# rapidshark.net
KiCad netlist of a schematic drawn in EAGLE
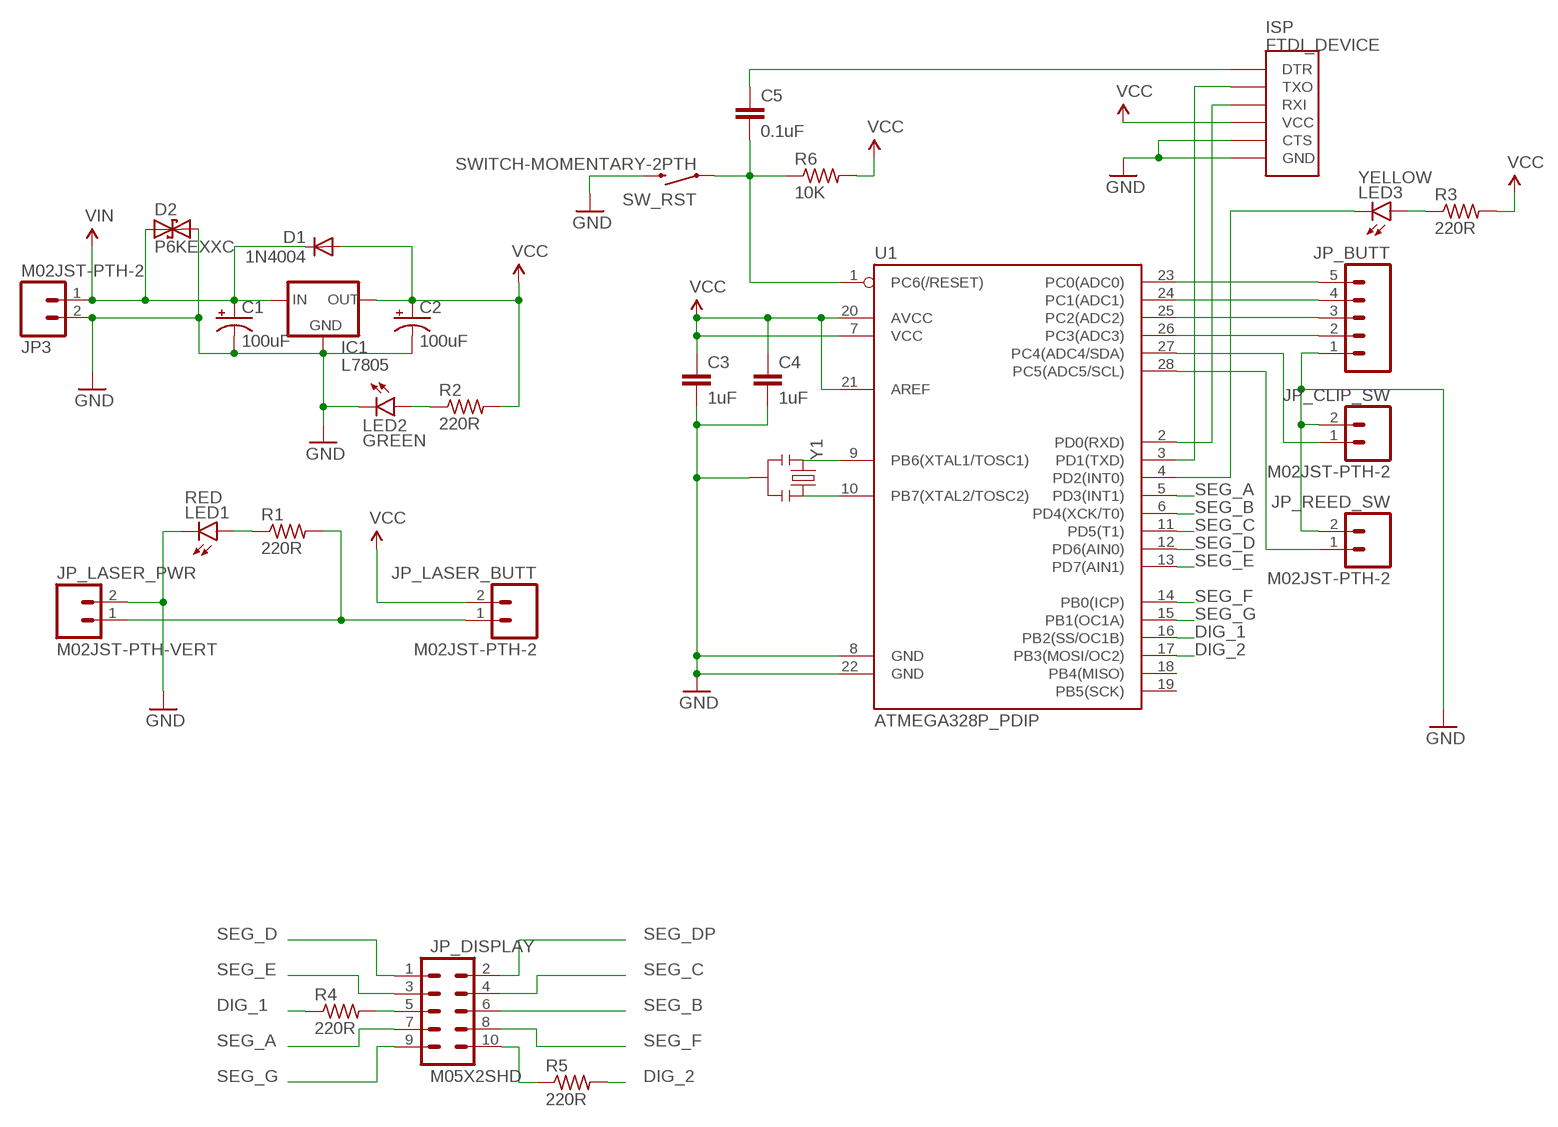
[diagram p0: schematic, sheet 1]

(export (version "E")
  (design (tool "Eeschema 10.0.6"))
  (components
    (comp (ref "C1")
      (value "100uF")
      (footprint "eagle-import:E2,5-6")
      (libsource (lib "eagle-import") (part "CPOL-USE2.5-6"))
    )
    (comp (ref "C2")
      (value "100uF")
      (footprint "eagle-import:E2,5-6")
      (libsource (lib "eagle-import") (part "CPOL-USE2.5-6"))
    )
    (comp (ref "C3")
      (value "1uF")
      (footprint "eagle-import:C025-025X050")
      (libsource (lib "eagle-import") (part "C-EU025-025X050"))
    )
    (comp (ref "C4")
      (value "1uF")
      (footprint "eagle-import:C050-024X044")
      (libsource (lib "eagle-import") (part "C-EU050-024X044"))
    )
    (comp (ref "C5")
      (value "0.1uF")
      (footprint "eagle-import:C050-024X044")
      (libsource (lib "eagle-import") (part "C-EU050-024X044"))
    )
    (comp (ref "D1")
      (value "1N4004")
      (footprint "eagle-import:DO41-10")
      (libsource (lib "eagle-import") (part "1N4004"))
    )
    (comp (ref "D2")
      (value "P6KEXXC")
      (footprint "eagle-import:CB417-15")
      (libsource (lib "eagle-import") (part "P6KEXXC"))
    )
    (comp (ref "IC1")
      (value "L7805")
      (footprint "eagle-import:TO-220-ALT")
      (libsource (lib "eagle-import") (part "V_REG_78XX-TO-220"))
    )
    (comp (ref "ISP")
      (value "FTDI_DEVICE")
      (footprint "eagle-import:FTDI_DEVICE_SIDE")
      (libsource (lib "eagle-import") (part "FTDI_DEVICE"))
    )
    (comp (ref "JP3")
      (value "M02JST-PTH-2")
      (footprint "eagle-import:JST-2-PTH")
      (libsource (lib "eagle-import") (part "M02JST-PTH-2"))
    )
    (comp (ref "JP_BUTT")
      (value "M05PTH")
      (footprint "eagle-import:1X05")
      (libsource (lib "eagle-import") (part "M05PTH"))
    )
    (comp (ref "JP_CLIP_SW")
      (value "M02JST-PTH-2")
      (footprint "eagle-import:JST-2-PTH")
      (libsource (lib "eagle-import") (part "M02JST-PTH-2"))
    )
    (comp (ref "JP_DISPLAY")
      (value "M05X2SHD")
      (footprint "eagle-import:2X5-SHROUDED")
      (libsource (lib "eagle-import") (part "M05X2SHD"))
    )
    (comp (ref "JP_LASER_BUTT")
      (value "M02JST-PTH-2")
      (footprint "eagle-import:JST-2-PTH")
      (libsource (lib "eagle-import") (part "M02JST-PTH-2"))
    )
    (comp (ref "JP_LASER_PWR")
      (value "M02JST-PTH-VERT")
      (footprint "eagle-import:JST-2-PTH-VERT")
      (libsource (lib "eagle-import") (part "M02JST-PTH-VERT"))
    )
    (comp (ref "JP_REED_SW")
      (value "M02JST-PTH-2")
      (footprint "eagle-import:JST-2-PTH")
      (libsource (lib "eagle-import") (part "M02JST-PTH-2"))
    )
    (comp (ref "LED1")
      (value "RED")
      (footprint "eagle-import:LED3MM")
      (libsource (lib "eagle-import") (part "LED3MM"))
    )
    (comp (ref "LED2")
      (value "GREEN")
      (footprint "eagle-import:LED3MM")
      (libsource (lib "eagle-import") (part "LED3MM"))
    )
    (comp (ref "LED3")
      (value "YELLOW")
      (footprint "eagle-import:LED3MM")
      (libsource (lib "eagle-import") (part "LED3MM"))
    )
    (comp (ref "R1")
      (value "220R")
      (footprint "eagle-import:0204_7")
      (libsource (lib "eagle-import") (part "R-US_0204/7"))
    )
    (comp (ref "R2")
      (value "220R")
      (footprint "eagle-import:0204_7")
      (libsource (lib "eagle-import") (part "R-US_0204/7"))
    )
    (comp (ref "R3")
      (value "220R")
      (footprint "eagle-import:0204_7")
      (libsource (lib "eagle-import") (part "R-US_0204/7"))
    )
    (comp (ref "R4")
      (value "220R")
      (footprint "eagle-import:0204_7")
      (libsource (lib "eagle-import") (part "R-US_0204/7"))
    )
    (comp (ref "R5")
      (value "220R")
      (footprint "eagle-import:0204_7")
      (libsource (lib "eagle-import") (part "R-US_0204/7"))
    )
    (comp (ref "R6")
      (value "10K")
      (footprint "eagle-import:0204_7")
      (libsource (lib "eagle-import") (part "R-US_0204/7"))
    )
    (comp (ref "SW_RST")
      (value "SWITCH-MOMENTARY-2PTH")
      (footprint "eagle-import:TACTILE-PTH")
      (libsource (lib "eagle-import") (part "SWITCH-MOMENTARY-2PTH"))
    )
    (comp (ref "U1")
      (value "ATMEGA328P_PDIP")
      (footprint "eagle-import:DIL28-3")
      (libsource (lib "eagle-import") (part "ATMEGA328P_PDIP"))
    )
    (comp (ref "Y1")
      (value "RESONATORPTH")
      (footprint "eagle-import:RESONATOR-PTH")
      (libsource (lib "eagle-import") (part "RESONATORPTH"))
    )
  )
  (nets
    (net (code "1") (name "/DIG_1") (class "Default")
      (node (ref "R4") (pin "1") (pinfunction "1_1") (pintype "passive"))
      (node (ref "U1") (pin "16") (pinfunction "PB2(SS/OC1B)_16") (pintype "bidirectional"))
    )
    (net (code "2") (name "/DIG_2") (class "Default")
      (node (ref "R5") (pin "2") (pinfunction "2_2") (pintype "passive"))
      (node (ref "U1") (pin "17") (pinfunction "PB3(MOSI/OC2)_17") (pintype "bidirectional"))
    )
    (net (code "3") (name "/SEG_A") (class "Default")
      (node (ref "JP_DISPLAY") (pin "7") (pinfunction "7_7") (pintype "passive"))
      (node (ref "U1") (pin "5") (pinfunction "PD3(INT1)_5") (pintype "bidirectional"))
    )
    (net (code "4") (name "/SEG_B") (class "Default")
      (node (ref "JP_DISPLAY") (pin "6") (pinfunction "6_6") (pintype "passive"))
      (node (ref "U1") (pin "6") (pinfunction "PD4(XCK/T0)_6") (pintype "bidirectional"))
    )
    (net (code "5") (name "/SEG_C") (class "Default")
      (node (ref "JP_DISPLAY") (pin "4") (pinfunction "4_4") (pintype "passive"))
      (node (ref "U1") (pin "11") (pinfunction "PD5(T1)_11") (pintype "bidirectional"))
    )
    (net (code "6") (name "/SEG_D") (class "Default")
      (node (ref "JP_DISPLAY") (pin "1") (pinfunction "1_1") (pintype "passive"))
      (node (ref "U1") (pin "12") (pinfunction "PD6(AIN0)_12") (pintype "bidirectional"))
    )
    (net (code "7") (name "/SEG_DP") (class "Default")
      (node (ref "JP_DISPLAY") (pin "2") (pinfunction "2_2") (pintype "passive"))
    )
    (net (code "8") (name "/SEG_E") (class "Default")
      (node (ref "JP_DISPLAY") (pin "3") (pinfunction "3_3") (pintype "passive"))
      (node (ref "U1") (pin "13") (pinfunction "PD7(AIN1)_13") (pintype "bidirectional"))
    )
    (net (code "9") (name "/SEG_F") (class "Default")
      (node (ref "JP_DISPLAY") (pin "8") (pinfunction "8_8") (pintype "passive"))
      (node (ref "U1") (pin "14") (pinfunction "PB0(ICP)_14") (pintype "bidirectional"))
    )
    (net (code "10") (name "/SEG_G") (class "Default")
      (node (ref "JP_DISPLAY") (pin "9") (pinfunction "9_9") (pintype "passive"))
      (node (ref "U1") (pin "15") (pinfunction "PB1(OC1A)_15") (pintype "bidirectional"))
    )
    (net (code "11") (name "GND") (class "Default")
      (node (ref "C1") (pin "-") (pinfunction "-_-") (pintype "passive"))
      (node (ref "C2") (pin "-") (pinfunction "-_-") (pintype "passive"))
      (node (ref "C3") (pin "2") (pinfunction "2_2") (pintype "passive"))
      (node (ref "C4") (pin "2") (pinfunction "2_2") (pintype "passive"))
      (node (ref "D2") (pin "C") (pinfunction "2_C") (pintype "passive"))
      (node (ref "IC1") (pin "GND") (pinfunction "GND_GND") (pintype "input"))
      (node (ref "ISP") (pin "P$5") (pinfunction "CTS_P$5") (pintype "bidirectional"))
      (node (ref "ISP") (pin "P$6") (pinfunction "GND_P$6") (pintype "bidirectional"))
      (node (ref "JP3") (pin "2") (pinfunction "2_2") (pintype "passive"))
      (node (ref "JP_BUTT") (pin "1") (pinfunction "1_1") (pintype "passive"))
      (node (ref "JP_CLIP_SW") (pin "2") (pinfunction "2_2") (pintype "passive"))
      (node (ref "JP_LASER_PWR") (pin "2") (pinfunction "2_2") (pintype "passive"))
      (node (ref "JP_REED_SW") (pin "2") (pinfunction "2_2") (pintype "passive"))
      (node (ref "LED1") (pin "K") (pinfunction "C_K") (pintype "passive"))
      (node (ref "LED2") (pin "K") (pinfunction "C_K") (pintype "passive"))
      (node (ref "SW_RST") (pin "3") (pinfunction "2_3") (pintype "passive"))
      (node (ref "U1") (pin "22") (pinfunction "GND_22") (pintype "bidirectional"))
      (node (ref "U1") (pin "8") (pinfunction "GND_8") (pintype "bidirectional"))
      (node (ref "Y1") (pin "2") (pinfunction "2_2") (pintype "passive"))
    )
    (net (code "12") (name "Net-(ISP-DTR)") (class "Default")
      (node (ref "C5") (pin "1") (pinfunction "1_1") (pintype "passive"))
      (node (ref "ISP") (pin "P$1") (pinfunction "DTR_P$1") (pintype "bidirectional"))
    )
    (net (code "13") (name "Net-(ISP-RXI)") (class "Default")
      (node (ref "ISP") (pin "P$3") (pinfunction "RXI_P$3") (pintype "bidirectional"))
      (node (ref "U1") (pin "2") (pinfunction "PD0(RXD)_2") (pintype "bidirectional"))
    )
    (net (code "14") (name "Net-(ISP-TXO)") (class "Default")
      (node (ref "ISP") (pin "P$2") (pinfunction "TXO_P$2") (pintype "bidirectional"))
      (node (ref "U1") (pin "3") (pinfunction "PD1(TXD)_3") (pintype "bidirectional"))
    )
    (net (code "15") (name "Net-(JP_DISPLAY-Pad5)") (class "Default")
      (node (ref "JP_DISPLAY") (pin "5") (pinfunction "5_5") (pintype "passive"))
      (node (ref "R4") (pin "2") (pinfunction "2_2") (pintype "passive"))
    )
    (net (code "16") (name "Net-(JP_DISPLAY-Pad10)") (class "Default")
      (node (ref "JP_DISPLAY") (pin "10") (pinfunction "10_10") (pintype "passive"))
      (node (ref "R5") (pin "1") (pinfunction "1_1") (pintype "passive"))
    )
    (net (code "17") (name "Net-(JP_LASER_BUTT-Pad1)") (class "Default")
      (node (ref "JP_LASER_BUTT") (pin "1") (pinfunction "1_1") (pintype "passive"))
      (node (ref "JP_LASER_PWR") (pin "1") (pinfunction "1_1") (pintype "passive"))
      (node (ref "R1") (pin "2") (pinfunction "2_2") (pintype "passive"))
    )
    (net (code "18") (name "Net-(LED1-PadA)") (class "Default")
      (node (ref "LED1") (pin "A") (pinfunction "A_A") (pintype "passive"))
      (node (ref "R1") (pin "1") (pinfunction "1_1") (pintype "passive"))
    )
    (net (code "19") (name "Net-(LED2-PadA)") (class "Default")
      (node (ref "LED2") (pin "A") (pinfunction "A_A") (pintype "passive"))
      (node (ref "R2") (pin "1") (pinfunction "1_1") (pintype "passive"))
    )
    (net (code "20") (name "Net-(LED3-C)") (class "Default")
      (node (ref "LED3") (pin "K") (pinfunction "C_K") (pintype "passive"))
      (node (ref "U1") (pin "4") (pinfunction "PD2(INT0)_4") (pintype "bidirectional"))
    )
    (net (code "21") (name "Net-(LED3-PadA)") (class "Default")
      (node (ref "LED3") (pin "A") (pinfunction "A_A") (pintype "passive"))
      (node (ref "R3") (pin "1") (pinfunction "1_1") (pintype "passive"))
    )
    (net (code "22") (name "Net-(U1-PB6(XTAL1{slash}TOSC1))") (class "Default")
      (node (ref "U1") (pin "9") (pinfunction "PB6(XTAL1/TOSC1)_9") (pintype "bidirectional"))
      (node (ref "Y1") (pin "3") (pinfunction "3_3") (pintype "passive"))
    )
    (net (code "23") (name "Net-(U1-PB7(XTAL2{slash}TOSC2))") (class "Default")
      (node (ref "U1") (pin "10") (pinfunction "PB7(XTAL2/TOSC2)_10") (pintype "bidirectional"))
      (node (ref "Y1") (pin "1") (pinfunction "1_1") (pintype "passive"))
    )
    (net (code "24") (name "Net-(U1-PC0(ADC0))") (class "Default")
      (node (ref "JP_BUTT") (pin "5") (pinfunction "5_5") (pintype "passive"))
      (node (ref "U1") (pin "23") (pinfunction "PC0(ADC0)_23") (pintype "bidirectional"))
    )
    (net (code "25") (name "Net-(U1-PC1(ADC1))") (class "Default")
      (node (ref "JP_BUTT") (pin "4") (pinfunction "4_4") (pintype "passive"))
      (node (ref "U1") (pin "24") (pinfunction "PC1(ADC1)_24") (pintype "bidirectional"))
    )
    (net (code "26") (name "Net-(U1-PC2(ADC2))") (class "Default")
      (node (ref "JP_BUTT") (pin "3") (pinfunction "3_3") (pintype "passive"))
      (node (ref "U1") (pin "25") (pinfunction "PC2(ADC2)_25") (pintype "bidirectional"))
    )
    (net (code "27") (name "Net-(U1-PC3(ADC3))") (class "Default")
      (node (ref "JP_BUTT") (pin "2") (pinfunction "2_2") (pintype "passive"))
      (node (ref "U1") (pin "26") (pinfunction "PC3(ADC3)_26") (pintype "bidirectional"))
    )
    (net (code "28") (name "Net-(U1-PC4(ADC4{slash}SDA))") (class "Default")
      (node (ref "JP_CLIP_SW") (pin "1") (pinfunction "1_1") (pintype "passive"))
      (node (ref "U1") (pin "27") (pinfunction "PC4(ADC4/SDA)_27") (pintype "bidirectional"))
    )
    (net (code "29") (name "Net-(U1-PC5(ADC5{slash}SCL))") (class "Default")
      (node (ref "JP_REED_SW") (pin "1") (pinfunction "1_1") (pintype "passive"))
      (node (ref "U1") (pin "28") (pinfunction "PC5(ADC5/SCL)_28") (pintype "bidirectional"))
    )
    (net (code "30") (name "Net-(U1-PC6({slash}RESET))") (class "Default")
      (node (ref "C5") (pin "2") (pinfunction "2_2") (pintype "passive"))
      (node (ref "R6") (pin "1") (pinfunction "1_1") (pintype "passive"))
      (node (ref "SW_RST") (pin "1") (pinfunction "1_1") (pintype "passive"))
      (node (ref "U1") (pin "1") (pinfunction "PC6(/RESET)_1") (pintype "bidirectional"))
    )
    (net (code "31") (name "VCC") (class "Default")
      (node (ref "C2") (pin "+") (pinfunction "+_+") (pintype "passive"))
      (node (ref "C3") (pin "1") (pinfunction "1_1") (pintype "passive"))
      (node (ref "C4") (pin "1") (pinfunction "1_1") (pintype "passive"))
      (node (ref "D1") (pin "A") (pinfunction "A_A") (pintype "passive"))
      (node (ref "IC1") (pin "OUT") (pinfunction "OUT_OUT") (pintype "output"))
      (node (ref "ISP") (pin "P$4") (pinfunction "VCC_P$4") (pintype "bidirectional"))
      (node (ref "JP_LASER_BUTT") (pin "2") (pinfunction "2_2") (pintype "passive"))
      (node (ref "R2") (pin "2") (pinfunction "2_2") (pintype "passive"))
      (node (ref "R3") (pin "2") (pinfunction "2_2") (pintype "passive"))
      (node (ref "R6") (pin "2") (pinfunction "2_2") (pintype "passive"))
      (node (ref "U1") (pin "20") (pinfunction "AVCC_20") (pintype "bidirectional"))
      (node (ref "U1") (pin "21") (pinfunction "AREF_21") (pintype "bidirectional"))
      (node (ref "U1") (pin "7") (pinfunction "VCC_7") (pintype "bidirectional"))
    )
    (net (code "32") (name "VIN") (class "Default")
      (node (ref "C1") (pin "+") (pinfunction "+_+") (pintype "passive"))
      (node (ref "D1") (pin "C") (pinfunction "C_C") (pintype "passive"))
      (node (ref "D2") (pin "A") (pinfunction "1_A") (pintype "passive"))
      (node (ref "IC1") (pin "IN") (pinfunction "IN_IN") (pintype "input"))
      (node (ref "JP3") (pin "1") (pinfunction "1_1") (pintype "passive"))
    )
    (net (code "33") (name "unconnected-(U1-PB4(MISO)-Pad18)") (class "Default")
      (node (ref "U1") (pin "18") (pinfunction "PB4(MISO)_18") (pintype "bidirectional"))
    )
    (net (code "34") (name "unconnected-(U1-PB5(SCK)-Pad19)") (class "Default")
      (node (ref "U1") (pin "19") (pinfunction "PB5(SCK)_19") (pintype "bidirectional"))
    )
  )
)
